# NixieDriver.net
KiCad netlist of a schematic drawn in EAGLE
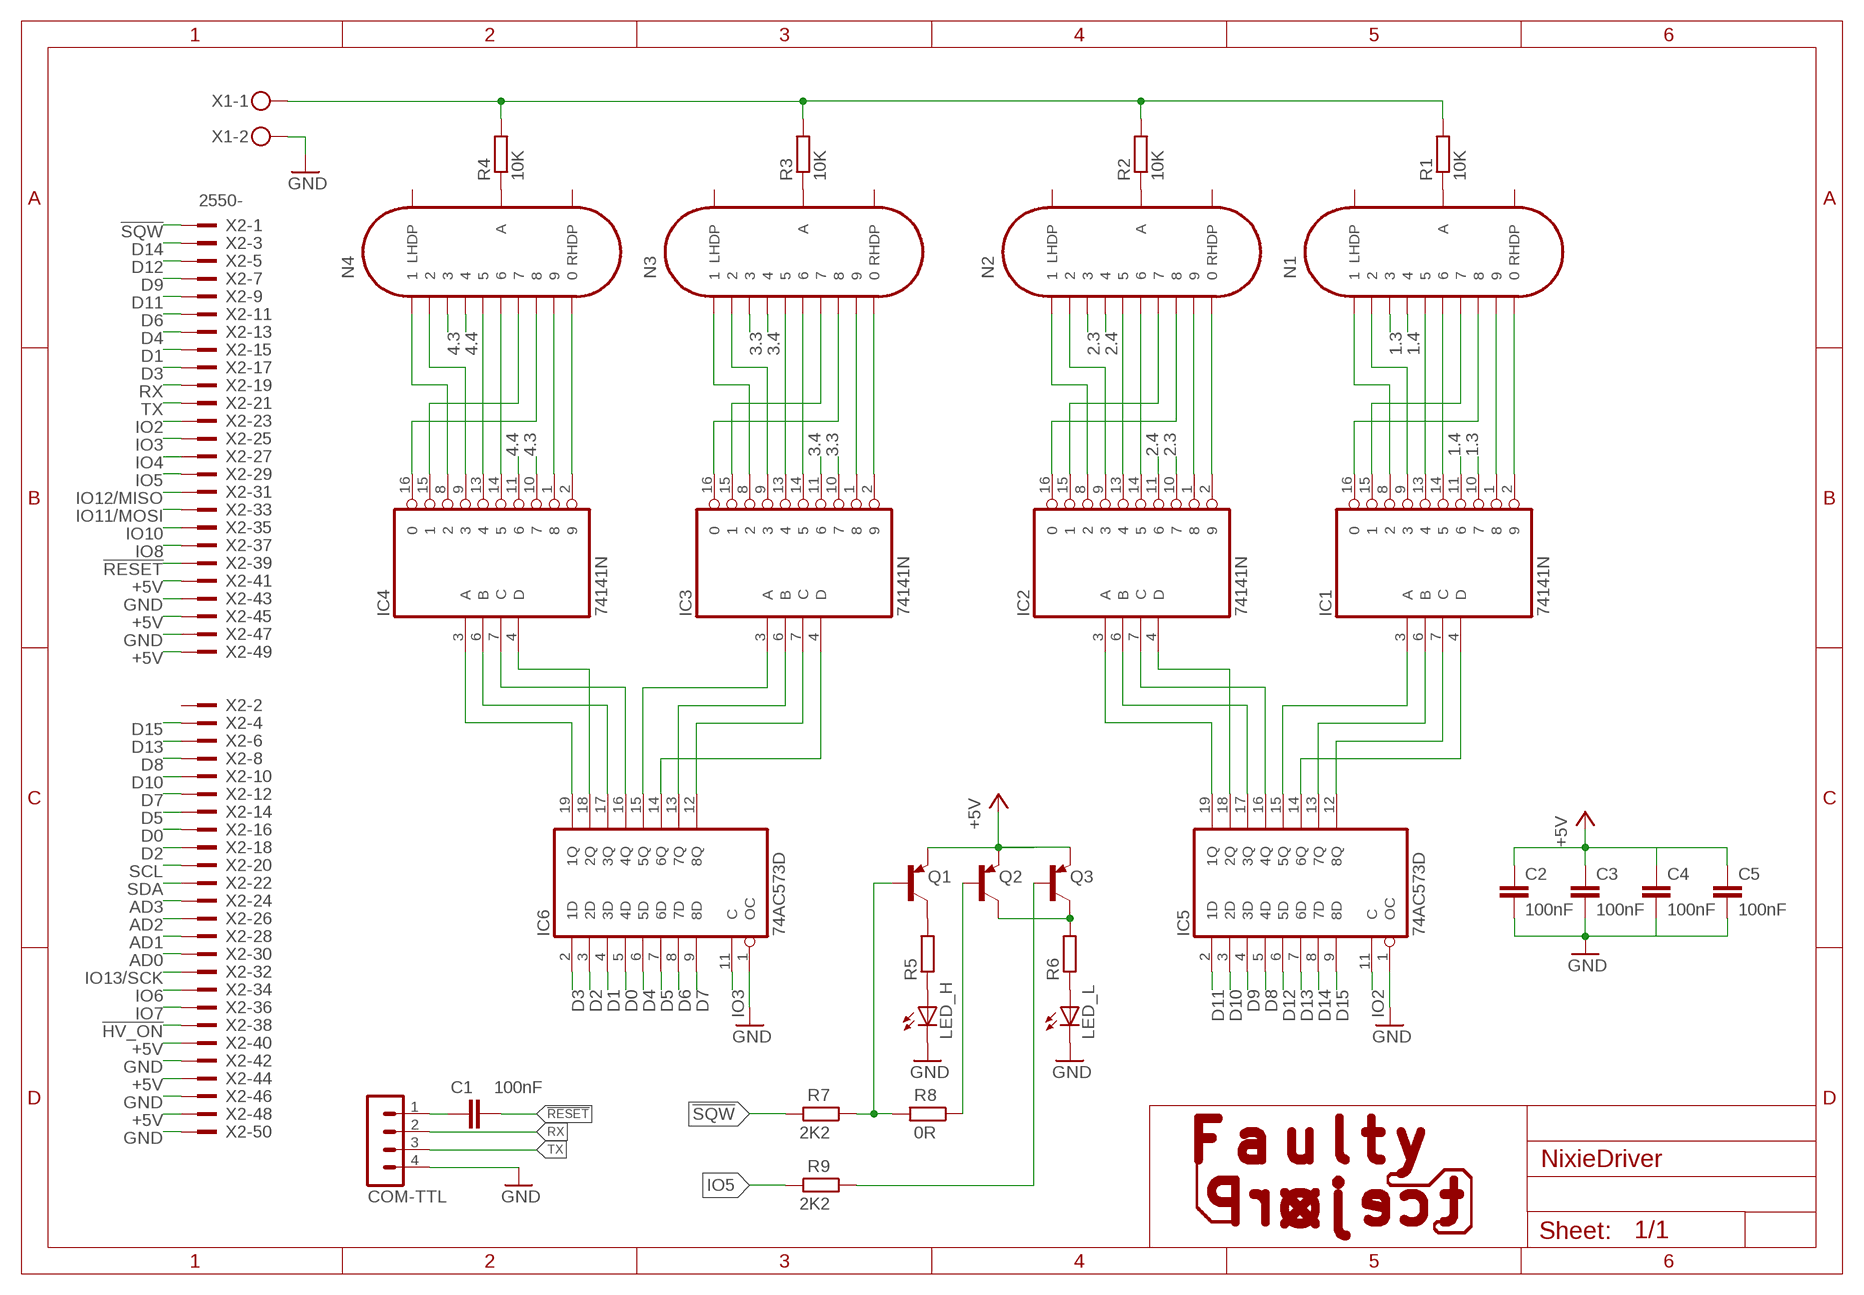
[diagram p0: schematic, sheet 1]

(export (version "E")
  (design (tool "Eeschema 10.0.6"))
  (components
    (comp (ref "C1")
      (value "100nF")
      (footprint "eagle-import:C1210")
      (libsource (lib "eagle-import") (part "C-EUC1210"))
    )
    (comp (ref "C2")
      (value "100nF")
      (footprint "eagle-import:C1210")
      (libsource (lib "eagle-import") (part "C-EUC1210"))
    )
    (comp (ref "C3")
      (value "100nF")
      (footprint "eagle-import:C1210")
      (libsource (lib "eagle-import") (part "C-EUC1210"))
    )
    (comp (ref "C4")
      (value "100nF")
      (footprint "eagle-import:C1210")
      (libsource (lib "eagle-import") (part "C-EUC1210"))
    )
    (comp (ref "C5")
      (value "100nF")
      (footprint "eagle-import:C1210")
      (libsource (lib "eagle-import") (part "C-EUC1210"))
    )
    (comp (ref "COM-TTL")
      (value "MA04-1")
      (footprint "eagle-import:MA04-1")
      (libsource (lib "eagle-import") (part "MA04-1"))
    )
    (comp (ref "IC1")
      (value "74141N")
      (footprint "eagle-import:DIL16")
      (libsource (lib "eagle-import") (part "74141N"))
    )
    (comp (ref "IC2")
      (value "74141N")
      (footprint "eagle-import:DIL16")
      (libsource (lib "eagle-import") (part "74141N"))
    )
    (comp (ref "IC3")
      (value "74141N")
      (footprint "eagle-import:DIL16")
      (libsource (lib "eagle-import") (part "74141N"))
    )
    (comp (ref "IC4")
      (value "74141N")
      (footprint "eagle-import:DIL16")
      (libsource (lib "eagle-import") (part "74141N"))
    )
    (comp (ref "IC5")
      (value "74AC573D")
      (footprint "eagle-import:SO20W")
      (libsource (lib "eagle-import") (part "74573DAC"))
    )
    (comp (ref "IC6")
      (value "74AC573D")
      (footprint "eagle-import:SO20W")
      (libsource (lib "eagle-import") (part "74573DAC"))
    )
    (comp (ref "LED_H")
      (value "LED5MM")
      (footprint "eagle-import:LED5MM")
      (libsource (lib "eagle-import") (part "LED5MM"))
    )
    (comp (ref "LED_L")
      (value "LED5MM")
      (footprint "eagle-import:LED5MM")
      (libsource (lib "eagle-import") (part "LED5MM"))
    )
    (comp (ref "N1")
      (value "IN-14")
      (footprint "eagle-import:IN-14")
      (libsource (lib "eagle-import") (part "IN-14"))
    )
    (comp (ref "N2")
      (value "IN-14")
      (footprint "eagle-import:IN-14")
      (libsource (lib "eagle-import") (part "IN-14"))
    )
    (comp (ref "N3")
      (value "IN-14")
      (footprint "eagle-import:IN-14")
      (libsource (lib "eagle-import") (part "IN-14"))
    )
    (comp (ref "N4")
      (value "IN-14")
      (footprint "eagle-import:IN-14")
      (libsource (lib "eagle-import") (part "IN-14"))
    )
    (comp (ref "Q1")
      (value "BF621-PNP-SOT98-BCE")
      (footprint "eagle-import:SOT89-BCE")
      (libsource (lib "eagle-import") (part "-PNP-SOT98-BCEBF621"))
    )
    (comp (ref "Q2")
      (value "BF621-PNP-SOT98-BCE")
      (footprint "eagle-import:SOT89-BCE")
      (libsource (lib "eagle-import") (part "-PNP-SOT98-BCEBF621"))
    )
    (comp (ref "Q3")
      (value "BF621-PNP-SOT98-BCE")
      (footprint "eagle-import:SOT89-BCE")
      (libsource (lib "eagle-import") (part "-PNP-SOT98-BCEBF621"))
    )
    (comp (ref "R1")
      (value "10K")
      (footprint "eagle-import:0309V")
      (libsource (lib "eagle-import") (part "R-EU_0309/V"))
    )
    (comp (ref "R2")
      (value "10K")
      (footprint "eagle-import:0309V")
      (libsource (lib "eagle-import") (part "R-EU_0309/V"))
    )
    (comp (ref "R3")
      (value "10K")
      (footprint "eagle-import:0309V")
      (libsource (lib "eagle-import") (part "R-EU_0309/V"))
    )
    (comp (ref "R4")
      (value "10K")
      (footprint "eagle-import:0309V")
      (libsource (lib "eagle-import") (part "R-EU_0309/V"))
    )
    (comp (ref "R5")
      (value "R-EU_M1206")
      (footprint "eagle-import:M1206")
      (libsource (lib "eagle-import") (part "R-EU_M1206"))
    )
    (comp (ref "R6")
      (value "R-EU_M1206")
      (footprint "eagle-import:M1206")
      (libsource (lib "eagle-import") (part "R-EU_M1206"))
    )
    (comp (ref "R7")
      (value "2K2")
      (footprint "eagle-import:M1406")
      (libsource (lib "eagle-import") (part "R-EU_M1406"))
    )
    (comp (ref "R8")
      (value "0R")
      (footprint "eagle-import:M1406")
      (libsource (lib "eagle-import") (part "R-EU_M1406"))
    )
    (comp (ref "R9")
      (value "2K2")
      (footprint "eagle-import:M1206")
      (libsource (lib "eagle-import") (part "R-EU_M1206"))
    )
    (comp (ref "X1")
      (value "MKDSN1,5/2-5,08")
      (footprint "eagle-import:MKDSN1,5_2-5,08")
      (libsource (lib "eagle-import") (part "MKDSN1,5/2-5,08"))
    )
    (comp (ref "X2")
      (value "2550-")
      (footprint "eagle-import:PAK100_2500-50")
      (libsource (lib "eagle-import") (part "2550-"))
    )
  )
  (nets
    (net (code "1") (name "+5V") (class "Default")
      (node (ref "C2") (pin "1") (pinfunction "1_1") (pintype "passive"))
      (node (ref "C3") (pin "1") (pinfunction "1_1") (pintype "passive"))
      (node (ref "C4") (pin "1") (pinfunction "1_1") (pintype "passive"))
      (node (ref "C5") (pin "1") (pinfunction "1_1") (pintype "passive"))
      (node (ref "Q1") (pin "E") (pinfunction "E_E") (pintype "passive"))
      (node (ref "Q2") (pin "E") (pinfunction "E_E") (pintype "passive"))
      (node (ref "Q3") (pin "E") (pinfunction "E_E") (pintype "passive"))
      (node (ref "X2") (pin "40") (pinfunction "KL_40") (pintype "passive"))
      (node (ref "X2") (pin "41") (pinfunction "KL_41") (pintype "passive"))
      (node (ref "X2") (pin "44") (pinfunction "KL_44") (pintype "passive"))
      (node (ref "X2") (pin "45") (pinfunction "KL_45") (pintype "passive"))
      (node (ref "X2") (pin "48") (pinfunction "KL_48") (pintype "passive"))
      (node (ref "X2") (pin "49") (pinfunction "KL_49") (pintype "passive"))
    )
    (net (code "2") (name "/1.3") (class "Default")
      (node (ref "IC1") (pin "10") (pinfunction "7_10") (pintype "open_collector"))
      (node (ref "N1") (pin "3") (pinfunction "3_3") (pintype "bidirectional"))
    )
    (net (code "3") (name "/1.4") (class "Default")
      (node (ref "IC1") (pin "11") (pinfunction "6_11") (pintype "open_collector"))
      (node (ref "N1") (pin "4") (pinfunction "4_4") (pintype "bidirectional"))
    )
    (net (code "4") (name "/2.3") (class "Default")
      (node (ref "IC2") (pin "10") (pinfunction "7_10") (pintype "open_collector"))
      (node (ref "N2") (pin "3") (pinfunction "3_3") (pintype "bidirectional"))
    )
    (net (code "5") (name "/2.4") (class "Default")
      (node (ref "IC2") (pin "11") (pinfunction "6_11") (pintype "open_collector"))
      (node (ref "N2") (pin "4") (pinfunction "4_4") (pintype "bidirectional"))
    )
    (net (code "6") (name "/3.3") (class "Default")
      (node (ref "IC3") (pin "10") (pinfunction "7_10") (pintype "open_collector"))
      (node (ref "N3") (pin "3") (pinfunction "3_3") (pintype "bidirectional"))
    )
    (net (code "7") (name "/3.4") (class "Default")
      (node (ref "IC3") (pin "11") (pinfunction "6_11") (pintype "open_collector"))
      (node (ref "N3") (pin "4") (pinfunction "4_4") (pintype "bidirectional"))
    )
    (net (code "8") (name "/4.3") (class "Default")
      (node (ref "IC4") (pin "10") (pinfunction "7_10") (pintype "open_collector"))
      (node (ref "N4") (pin "3") (pinfunction "3_3") (pintype "bidirectional"))
    )
    (net (code "9") (name "/4.4") (class "Default")
      (node (ref "IC4") (pin "11") (pinfunction "6_11") (pintype "open_collector"))
      (node (ref "N4") (pin "4") (pinfunction "4_4") (pintype "bidirectional"))
    )
    (net (code "10") (name "/AD0") (class "Default")
      (node (ref "X2") (pin "30") (pinfunction "KL_30") (pintype "passive"))
    )
    (net (code "11") (name "/AD1") (class "Default")
      (node (ref "X2") (pin "28") (pinfunction "KL_28") (pintype "passive"))
    )
    (net (code "12") (name "/AD2") (class "Default")
      (node (ref "X2") (pin "26") (pinfunction "KL_26") (pintype "passive"))
    )
    (net (code "13") (name "/AD3") (class "Default")
      (node (ref "X2") (pin "24") (pinfunction "KL_24") (pintype "passive"))
    )
    (net (code "14") (name "/D0") (class "Default")
      (node (ref "IC6") (pin "5") (pinfunction "4D_5") (pintype "input"))
      (node (ref "X2") (pin "16") (pinfunction "KL_16") (pintype "passive"))
    )
    (net (code "15") (name "/D1") (class "Default")
      (node (ref "IC6") (pin "4") (pinfunction "3D_4") (pintype "input"))
      (node (ref "X2") (pin "15") (pinfunction "KL_15") (pintype "passive"))
    )
    (net (code "16") (name "/D2") (class "Default")
      (node (ref "IC6") (pin "3") (pinfunction "2D_3") (pintype "input"))
      (node (ref "X2") (pin "18") (pinfunction "KL_18") (pintype "passive"))
    )
    (net (code "17") (name "/D3") (class "Default")
      (node (ref "IC6") (pin "2") (pinfunction "1D_2") (pintype "input"))
      (node (ref "X2") (pin "17") (pinfunction "KL_17") (pintype "passive"))
    )
    (net (code "18") (name "/D4") (class "Default")
      (node (ref "IC6") (pin "6") (pinfunction "5D_6") (pintype "input"))
      (node (ref "X2") (pin "13") (pinfunction "KL_13") (pintype "passive"))
    )
    (net (code "19") (name "/D5") (class "Default")
      (node (ref "IC6") (pin "7") (pinfunction "6D_7") (pintype "input"))
      (node (ref "X2") (pin "14") (pinfunction "KL_14") (pintype "passive"))
    )
    (net (code "20") (name "/D6") (class "Default")
      (node (ref "IC6") (pin "8") (pinfunction "7D_8") (pintype "input"))
      (node (ref "X2") (pin "11") (pinfunction "KL_11") (pintype "passive"))
    )
    (net (code "21") (name "/D7") (class "Default")
      (node (ref "IC6") (pin "9") (pinfunction "8D_9") (pintype "input"))
      (node (ref "X2") (pin "12") (pinfunction "KL_12") (pintype "passive"))
    )
    (net (code "22") (name "/D8") (class "Default")
      (node (ref "IC5") (pin "5") (pinfunction "4D_5") (pintype "input"))
      (node (ref "X2") (pin "8") (pinfunction "KL_8") (pintype "passive"))
    )
    (net (code "23") (name "/D9") (class "Default")
      (node (ref "IC5") (pin "4") (pinfunction "3D_4") (pintype "input"))
      (node (ref "X2") (pin "7") (pinfunction "KL_7") (pintype "passive"))
    )
    (net (code "24") (name "/D10") (class "Default")
      (node (ref "IC5") (pin "3") (pinfunction "2D_3") (pintype "input"))
      (node (ref "X2") (pin "10") (pinfunction "KL_10") (pintype "passive"))
    )
    (net (code "25") (name "/D11") (class "Default")
      (node (ref "IC5") (pin "2") (pinfunction "1D_2") (pintype "input"))
      (node (ref "X2") (pin "9") (pinfunction "KL_9") (pintype "passive"))
    )
    (net (code "26") (name "/D12") (class "Default")
      (node (ref "IC5") (pin "6") (pinfunction "5D_6") (pintype "input"))
      (node (ref "X2") (pin "5") (pinfunction "KL_5") (pintype "passive"))
    )
    (net (code "27") (name "/D13") (class "Default")
      (node (ref "IC5") (pin "7") (pinfunction "6D_7") (pintype "input"))
      (node (ref "X2") (pin "6") (pinfunction "KL_6") (pintype "passive"))
    )
    (net (code "28") (name "/D14") (class "Default")
      (node (ref "IC5") (pin "8") (pinfunction "7D_8") (pintype "input"))
      (node (ref "X2") (pin "3") (pinfunction "KL_3") (pintype "passive"))
    )
    (net (code "29") (name "/D15") (class "Default")
      (node (ref "IC5") (pin "9") (pinfunction "8D_9") (pintype "input"))
      (node (ref "X2") (pin "4") (pinfunction "KL_4") (pintype "passive"))
    )
    (net (code "30") (name "/IO2") (class "Default")
      (node (ref "IC5") (pin "11") (pinfunction "C_11") (pintype "input"))
      (node (ref "X2") (pin "23") (pinfunction "KL_23") (pintype "passive"))
    )
    (net (code "31") (name "/IO3") (class "Default")
      (node (ref "IC6") (pin "11") (pinfunction "C_11") (pintype "input"))
      (node (ref "X2") (pin "25") (pinfunction "KL_25") (pintype "passive"))
    )
    (net (code "32") (name "/IO4") (class "Default")
      (node (ref "X2") (pin "27") (pinfunction "KL_27") (pintype "passive"))
    )
    (net (code "33") (name "/IO6") (class "Default")
      (node (ref "X2") (pin "34") (pinfunction "KL_34") (pintype "passive"))
    )
    (net (code "34") (name "/IO7") (class "Default")
      (node (ref "X2") (pin "36") (pinfunction "KL_36") (pintype "passive"))
    )
    (net (code "35") (name "/IO8") (class "Default")
      (node (ref "X2") (pin "37") (pinfunction "KL_37") (pintype "passive"))
    )
    (net (code "36") (name "/IO10") (class "Default")
      (node (ref "X2") (pin "35") (pinfunction "KL_35") (pintype "passive"))
    )
    (net (code "37") (name "/IO11{slash}MOSI") (class "Default")
      (node (ref "X2") (pin "33") (pinfunction "KL_33") (pintype "passive"))
    )
    (net (code "38") (name "/IO12{slash}MISO") (class "Default")
      (node (ref "X2") (pin "31") (pinfunction "KL_31") (pintype "passive"))
    )
    (net (code "39") (name "/IO13{slash}SCK") (class "Default")
      (node (ref "X2") (pin "32") (pinfunction "KL_32") (pintype "passive"))
    )
    (net (code "40") (name "/SCL") (class "Default")
      (node (ref "X2") (pin "20") (pinfunction "KL_20") (pintype "passive"))
    )
    (net (code "41") (name "/SDA") (class "Default")
      (node (ref "X2") (pin "22") (pinfunction "KL_22") (pintype "passive"))
    )
    (net (code "42") (name "/~{HV_ON}") (class "Default")
      (node (ref "X2") (pin "38") (pinfunction "KL_38") (pintype "passive"))
    )
    (net (code "43") (name "/~{RESET}") (class "Default")
      (node (ref "C1") (pin "2") (pinfunction "2_2") (pintype "passive"))
      (node (ref "X2") (pin "39") (pinfunction "KL_39") (pintype "passive"))
    )
    (net (code "44") (name "/~{SQW}") (class "Default")
      (node (ref "R7") (pin "2") (pinfunction "2_2") (pintype "passive"))
      (node (ref "X2") (pin "1") (pinfunction "KL_1") (pintype "passive"))
    )
    (net (code "45") (name "GND") (class "Default")
      (node (ref "C2") (pin "2") (pinfunction "2_2") (pintype "passive"))
      (node (ref "C3") (pin "2") (pinfunction "2_2") (pintype "passive"))
      (node (ref "C4") (pin "2") (pinfunction "2_2") (pintype "passive"))
      (node (ref "C5") (pin "2") (pinfunction "2_2") (pintype "passive"))
      (node (ref "COM-TTL") (pin "4") (pinfunction "4_4") (pintype "passive"))
      (node (ref "IC5") (pin "1") (pinfunction "OC_1") (pintype "input"))
      (node (ref "IC6") (pin "1") (pinfunction "OC_1") (pintype "input"))
      (node (ref "LED_H") (pin "K") (pinfunction "C_K") (pintype "passive"))
      (node (ref "LED_L") (pin "K") (pinfunction "C_K") (pintype "passive"))
      (node (ref "X1") (pin "2") (pinfunction "KL_2") (pintype "passive"))
      (node (ref "X2") (pin "42") (pinfunction "KL_42") (pintype "passive"))
      (node (ref "X2") (pin "43") (pinfunction "KL_43") (pintype "passive"))
      (node (ref "X2") (pin "46") (pinfunction "KL_46") (pintype "passive"))
      (node (ref "X2") (pin "47") (pinfunction "KL_47") (pintype "passive"))
      (node (ref "X2") (pin "50") (pinfunction "KL_50") (pintype "passive"))
    )
    (net (code "46") (name "IO5") (class "Default")
      (node (ref "R9") (pin "2") (pinfunction "2_2") (pintype "passive"))
      (node (ref "X2") (pin "29") (pinfunction "KL_29") (pintype "passive"))
    )
    (net (code "47") (name "Net-(C1-Pad1)") (class "Default")
      (node (ref "C1") (pin "1") (pinfunction "1_1") (pintype "passive"))
      (node (ref "COM-TTL") (pin "1") (pinfunction "1_1") (pintype "passive"))
    )
    (net (code "48") (name "Net-(IC1A-0)") (class "Default")
      (node (ref "IC1") (pin "16") (pinfunction "0_16") (pintype "open_collector"))
      (node (ref "N1") (pin "8") (pinfunction "8_8") (pintype "bidirectional"))
    )
    (net (code "49") (name "Net-(IC1A-1)") (class "Default")
      (node (ref "IC1") (pin "15") (pinfunction "1_15") (pintype "open_collector"))
      (node (ref "N1") (pin "7") (pinfunction "7_7") (pintype "bidirectional"))
    )
    (net (code "50") (name "Net-(IC1A-2)") (class "Default")
      (node (ref "IC1") (pin "8") (pinfunction "2_8") (pintype "open_collector"))
      (node (ref "N1") (pin "1") (pinfunction "1_1") (pintype "bidirectional"))
    )
    (net (code "51") (name "Net-(IC1A-3)") (class "Default")
      (node (ref "IC1") (pin "9") (pinfunction "3_9") (pintype "open_collector"))
      (node (ref "N1") (pin "2") (pinfunction "2_2") (pintype "bidirectional"))
    )
    (net (code "52") (name "Net-(IC1A-4)") (class "Default")
      (node (ref "IC1") (pin "13") (pinfunction "4_13") (pintype "open_collector"))
      (node (ref "N1") (pin "5") (pinfunction "5_5") (pintype "bidirectional"))
    )
    (net (code "53") (name "Net-(IC1A-5)") (class "Default")
      (node (ref "IC1") (pin "14") (pinfunction "5_14") (pintype "open_collector"))
      (node (ref "N1") (pin "6") (pinfunction "6_6") (pintype "bidirectional"))
    )
    (net (code "54") (name "Net-(IC1A-8)") (class "Default")
      (node (ref "IC1") (pin "1") (pinfunction "8_1") (pintype "open_collector"))
      (node (ref "N1") (pin "9") (pinfunction "9_9") (pintype "bidirectional"))
    )
    (net (code "55") (name "Net-(IC1A-9)") (class "Default")
      (node (ref "IC1") (pin "2") (pinfunction "9_2") (pintype "open_collector"))
      (node (ref "N1") (pin "0") (pinfunction "0_0") (pintype "bidirectional"))
    )
    (net (code "56") (name "Net-(IC1A-A)") (class "Default")
      (node (ref "IC1") (pin "3") (pinfunction "A_3") (pintype "input"))
      (node (ref "IC5") (pin "15") (pinfunction "5Q_15") (pintype "tri_state"))
    )
    (net (code "57") (name "Net-(IC1A-B)") (class "Default")
      (node (ref "IC1") (pin "6") (pinfunction "B_6") (pintype "input"))
      (node (ref "IC5") (pin "13") (pinfunction "7Q_13") (pintype "tri_state"))
    )
    (net (code "58") (name "Net-(IC1A-C)") (class "Default")
      (node (ref "IC1") (pin "7") (pinfunction "C_7") (pintype "input"))
      (node (ref "IC5") (pin "12") (pinfunction "8Q_12") (pintype "tri_state"))
    )
    (net (code "59") (name "Net-(IC1A-D)") (class "Default")
      (node (ref "IC1") (pin "4") (pinfunction "D_4") (pintype "input"))
      (node (ref "IC5") (pin "14") (pinfunction "6Q_14") (pintype "tri_state"))
    )
    (net (code "60") (name "Net-(IC2A-0)") (class "Default")
      (node (ref "IC2") (pin "16") (pinfunction "0_16") (pintype "open_collector"))
      (node (ref "N2") (pin "8") (pinfunction "8_8") (pintype "bidirectional"))
    )
    (net (code "61") (name "Net-(IC2A-1)") (class "Default")
      (node (ref "IC2") (pin "15") (pinfunction "1_15") (pintype "open_collector"))
      (node (ref "N2") (pin "7") (pinfunction "7_7") (pintype "bidirectional"))
    )
    (net (code "62") (name "Net-(IC2A-2)") (class "Default")
      (node (ref "IC2") (pin "8") (pinfunction "2_8") (pintype "open_collector"))
      (node (ref "N2") (pin "1") (pinfunction "1_1") (pintype "bidirectional"))
    )
    (net (code "63") (name "Net-(IC2A-3)") (class "Default")
      (node (ref "IC2") (pin "9") (pinfunction "3_9") (pintype "open_collector"))
      (node (ref "N2") (pin "2") (pinfunction "2_2") (pintype "bidirectional"))
    )
    (net (code "64") (name "Net-(IC2A-4)") (class "Default")
      (node (ref "IC2") (pin "13") (pinfunction "4_13") (pintype "open_collector"))
      (node (ref "N2") (pin "5") (pinfunction "5_5") (pintype "bidirectional"))
    )
    (net (code "65") (name "Net-(IC2A-5)") (class "Default")
      (node (ref "IC2") (pin "14") (pinfunction "5_14") (pintype "open_collector"))
      (node (ref "N2") (pin "6") (pinfunction "6_6") (pintype "bidirectional"))
    )
    (net (code "66") (name "Net-(IC2A-8)") (class "Default")
      (node (ref "IC2") (pin "1") (pinfunction "8_1") (pintype "open_collector"))
      (node (ref "N2") (pin "9") (pinfunction "9_9") (pintype "bidirectional"))
    )
    (net (code "67") (name "Net-(IC2A-9)") (class "Default")
      (node (ref "IC2") (pin "2") (pinfunction "9_2") (pintype "open_collector"))
      (node (ref "N2") (pin "0") (pinfunction "0_0") (pintype "bidirectional"))
    )
    (net (code "68") (name "Net-(IC2A-A)") (class "Default")
      (node (ref "IC2") (pin "3") (pinfunction "A_3") (pintype "input"))
      (node (ref "IC5") (pin "19") (pinfunction "1Q_19") (pintype "tri_state"))
    )
    (net (code "69") (name "Net-(IC2A-B)") (class "Default")
      (node (ref "IC2") (pin "6") (pinfunction "B_6") (pintype "input"))
      (node (ref "IC5") (pin "17") (pinfunction "3Q_17") (pintype "tri_state"))
    )
    (net (code "70") (name "Net-(IC2A-C)") (class "Default")
      (node (ref "IC2") (pin "7") (pinfunction "C_7") (pintype "input"))
      (node (ref "IC5") (pin "16") (pinfunction "4Q_16") (pintype "tri_state"))
    )
    (net (code "71") (name "Net-(IC2A-D)") (class "Default")
      (node (ref "IC2") (pin "4") (pinfunction "D_4") (pintype "input"))
      (node (ref "IC5") (pin "18") (pinfunction "2Q_18") (pintype "tri_state"))
    )
    (net (code "72") (name "Net-(IC3A-0)") (class "Default")
      (node (ref "IC3") (pin "16") (pinfunction "0_16") (pintype "open_collector"))
      (node (ref "N3") (pin "8") (pinfunction "8_8") (pintype "bidirectional"))
    )
    (net (code "73") (name "Net-(IC3A-1)") (class "Default")
      (node (ref "IC3") (pin "15") (pinfunction "1_15") (pintype "open_collector"))
      (node (ref "N3") (pin "7") (pinfunction "7_7") (pintype "bidirectional"))
    )
    (net (code "74") (name "Net-(IC3A-2)") (class "Default")
      (node (ref "IC3") (pin "8") (pinfunction "2_8") (pintype "open_collector"))
      (node (ref "N3") (pin "1") (pinfunction "1_1") (pintype "bidirectional"))
    )
    (net (code "75") (name "Net-(IC3A-3)") (class "Default")
      (node (ref "IC3") (pin "9") (pinfunction "3_9") (pintype "open_collector"))
      (node (ref "N3") (pin "2") (pinfunction "2_2") (pintype "bidirectional"))
    )
    (net (code "76") (name "Net-(IC3A-4)") (class "Default")
      (node (ref "IC3") (pin "13") (pinfunction "4_13") (pintype "open_collector"))
      (node (ref "N3") (pin "5") (pinfunction "5_5") (pintype "bidirectional"))
    )
    (net (code "77") (name "Net-(IC3A-5)") (class "Default")
      (node (ref "IC3") (pin "14") (pinfunction "5_14") (pintype "open_collector"))
      (node (ref "N3") (pin "6") (pinfunction "6_6") (pintype "bidirectional"))
    )
    (net (code "78") (name "Net-(IC3A-8)") (class "Default")
      (node (ref "IC3") (pin "1") (pinfunction "8_1") (pintype "open_collector"))
      (node (ref "N3") (pin "9") (pinfunction "9_9") (pintype "bidirectional"))
    )
    (net (code "79") (name "Net-(IC3A-9)") (class "Default")
      (node (ref "IC3") (pin "2") (pinfunction "9_2") (pintype "open_collector"))
      (node (ref "N3") (pin "0") (pinfunction "0_0") (pintype "bidirectional"))
    )
    (net (code "80") (name "Net-(IC3A-A)") (class "Default")
      (node (ref "IC3") (pin "3") (pinfunction "A_3") (pintype "input"))
      (node (ref "IC6") (pin "15") (pinfunction "5Q_15") (pintype "tri_state"))
    )
    (net (code "81") (name "Net-(IC3A-B)") (class "Default")
      (node (ref "IC3") (pin "6") (pinfunction "B_6") (pintype "input"))
      (node (ref "IC6") (pin "13") (pinfunction "7Q_13") (pintype "tri_state"))
    )
    (net (code "82") (name "Net-(IC3A-C)") (class "Default")
      (node (ref "IC3") (pin "7") (pinfunction "C_7") (pintype "input"))
      (node (ref "IC6") (pin "12") (pinfunction "8Q_12") (pintype "tri_state"))
    )
    (net (code "83") (name "Net-(IC3A-D)") (class "Default")
      (node (ref "IC3") (pin "4") (pinfunction "D_4") (pintype "input"))
      (node (ref "IC6") (pin "14") (pinfunction "6Q_14") (pintype "tri_state"))
    )
    (net (code "84") (name "Net-(IC4A-0)") (class "Default")
      (node (ref "IC4") (pin "16") (pinfunction "0_16") (pintype "open_collector"))
      (node (ref "N4") (pin "8") (pinfunction "8_8") (pintype "bidirectional"))
    )
    (net (code "85") (name "Net-(IC4A-1)") (class "Default")
      (node (ref "IC4") (pin "15") (pinfunction "1_15") (pintype "open_collector"))
      (node (ref "N4") (pin "7") (pinfunction "7_7") (pintype "bidirectional"))
    )
    (net (code "86") (name "Net-(IC4A-2)") (class "Default")
      (node (ref "IC4") (pin "8") (pinfunction "2_8") (pintype "open_collector"))
      (node (ref "N4") (pin "1") (pinfunction "1_1") (pintype "bidirectional"))
    )
    (net (code "87") (name "Net-(IC4A-3)") (class "Default")
      (node (ref "IC4") (pin "9") (pinfunction "3_9") (pintype "open_collector"))
      (node (ref "N4") (pin "2") (pinfunction "2_2") (pintype "bidirectional"))
    )
    (net (code "88") (name "Net-(IC4A-4)") (class "Default")
      (node (ref "IC4") (pin "13") (pinfunction "4_13") (pintype "open_collector"))
      (node (ref "N4") (pin "5") (pinfunction "5_5") (pintype "bidirectional"))
    )
    (net (code "89") (name "Net-(IC4A-5)") (class "Default")
      (node (ref "IC4") (pin "14") (pinfunction "5_14") (pintype "open_collector"))
      (node (ref "N4") (pin "6") (pinfunction "6_6") (pintype "bidirectional"))
    )
    (net (code "90") (name "Net-(IC4A-8)") (class "Default")
      (node (ref "IC4") (pin "1") (pinfunction "8_1") (pintype "open_collector"))
      (node (ref "N4") (pin "9") (pinfunction "9_9") (pintype "bidirectional"))
    )
    (net (code "91") (name "Net-(IC4A-9)") (class "Default")
      (node (ref "IC4") (pin "2") (pinfunction "9_2") (pintype "open_collector"))
      (node (ref "N4") (pin "0") (pinfunction "0_0") (pintype "bidirectional"))
    )
    (net (code "92") (name "Net-(IC4A-A)") (class "Default")
      (node (ref "IC4") (pin "3") (pinfunction "A_3") (pintype "input"))
      (node (ref "IC6") (pin "19") (pinfunction "1Q_19") (pintype "tri_state"))
    )
    (net (code "93") (name "Net-(IC4A-B)") (class "Default")
      (node (ref "IC4") (pin "6") (pinfunction "B_6") (pintype "input"))
      (node (ref "IC6") (pin "17") (pinfunction "3Q_17") (pintype "tri_state"))
    )
    (net (code "94") (name "Net-(IC4A-C)") (class "Default")
      (node (ref "IC4") (pin "7") (pinfunction "C_7") (pintype "input"))
      (node (ref "IC6") (pin "16") (pinfunction "4Q_16") (pintype "tri_state"))
    )
    (net (code "95") (name "Net-(IC4A-D)") (class "Default")
      (node (ref "IC4") (pin "4") (pinfunction "D_4") (pintype "input"))
      (node (ref "IC6") (pin "18") (pinfunction "2Q_18") (pintype "tri_state"))
    )
    (net (code "96") (name "Net-(LED_H-PadA)") (class "Default")
      (node (ref "LED_H") (pin "A") (pinfunction "A_A") (pintype "passive"))
      (node (ref "R5") (pin "1") (pinfunction "1_1") (pintype "passive"))
    )
    (net (code "97") (name "Net-(LED_L-PadA)") (class "Default")
      (node (ref "LED_L") (pin "A") (pinfunction "A_A") (pintype "passive"))
      (node (ref "R6") (pin "1") (pinfunction "1_1") (pintype "passive"))
    )
    (net (code "98") (name "Net-(N1-PadA)") (class "Default")
      (node (ref "N1") (pin "A") (pinfunction "A_A") (pintype "bidirectional"))
      (node (ref "R1") (pin "1") (pinfunction "1_1") (pintype "passive"))
    )
    (net (code "99") (name "Net-(N2-PadA)") (class "Default")
      (node (ref "N2") (pin "A") (pinfunction "A_A") (pintype "bidirectional"))
      (node (ref "R2") (pin "1") (pinfunction "1_1") (pintype "passive"))
    )
    (net (code "100") (name "Net-(N3-PadA)") (class "Default")
      (node (ref "N3") (pin "A") (pinfunction "A_A") (pintype "bidirectional"))
      (node (ref "R3") (pin "1") (pinfunction "1_1") (pintype "passive"))
    )
    (net (code "101") (name "Net-(N4-PadA)") (class "Default")
      (node (ref "N4") (pin "A") (pinfunction "A_A") (pintype "bidirectional"))
      (node (ref "R4") (pin "1") (pinfunction "1_1") (pintype "passive"))
    )
    (net (code "102") (name "Net-(Q1-PadB)") (class "Default")
      (node (ref "Q1") (pin "B") (pinfunction "B_B") (pintype "passive"))
      (node (ref "R7") (pin "1") (pinfunction "1_1") (pintype "passive"))
      (node (ref "R8") (pin "2") (pinfunction "2_2") (pintype "passive"))
    )
    (net (code "103") (name "Net-(Q1-PadC)") (class "Default")
      (node (ref "Q1") (pin "C") (pinfunction "C_C") (pintype "passive"))
      (node (ref "R5") (pin "2") (pinfunction "2_2") (pintype "passive"))
    )
    (net (code "104") (name "Net-(Q2-PadB)") (class "Default")
      (node (ref "Q2") (pin "B") (pinfunction "B_B") (pintype "passive"))
      (node (ref "R8") (pin "1") (pinfunction "1_1") (pintype "passive"))
    )
    (net (code "105") (name "Net-(Q2-PadC)") (class "Default")
      (node (ref "Q2") (pin "C") (pinfunction "C_C") (pintype "passive"))
      (node (ref "Q3") (pin "C") (pinfunction "C_C") (pintype "passive"))
      (node (ref "R6") (pin "2") (pinfunction "2_2") (pintype "passive"))
    )
    (net (code "106") (name "Net-(Q3-PadB)") (class "Default")
      (node (ref "Q3") (pin "B") (pinfunction "B_B") (pintype "passive"))
      (node (ref "R9") (pin "1") (pinfunction "1_1") (pintype "passive"))
    )
    (net (code "107") (name "Net-(X1A-KL)") (class "Default")
      (node (ref "R1") (pin "2") (pinfunction "2_2") (pintype "passive"))
      (node (ref "R2") (pin "2") (pinfunction "2_2") (pintype "passive"))
      (node (ref "R3") (pin "2") (pinfunction "2_2") (pintype "passive"))
      (node (ref "R4") (pin "2") (pinfunction "2_2") (pintype "passive"))
      (node (ref "X1") (pin "1") (pinfunction "KL_1") (pintype "passive"))
    )
    (net (code "108") (name "RX") (class "Default")
      (node (ref "COM-TTL") (pin "2") (pinfunction "2_2") (pintype "passive"))
      (node (ref "X2") (pin "19") (pinfunction "KL_19") (pintype "passive"))
    )
    (net (code "109") (name "TX") (class "Default")
      (node (ref "COM-TTL") (pin "3") (pinfunction "3_3") (pintype "passive"))
      (node (ref "X2") (pin "21") (pinfunction "KL_21") (pintype "passive"))
    )
    (net (code "110") (name "unconnected-(N1-PadLHDP)") (class "Default")
      (node (ref "N1") (pin "LHDP") (pinfunction "LHDP_LHDP") (pintype "bidirectional"))
    )
    (net (code "111") (name "unconnected-(N1-PadRHDP)") (class "Default")
      (node (ref "N1") (pin "RHDP") (pinfunction "RHDP_RHDP") (pintype "bidirectional"))
    )
    (net (code "112") (name "unconnected-(N2-PadLHDP)") (class "Default")
      (node (ref "N2") (pin "LHDP") (pinfunction "LHDP_LHDP") (pintype "bidirectional"))
    )
    (net (code "113") (name "unconnected-(N2-PadRHDP)") (class "Default")
      (node (ref "N2") (pin "RHDP") (pinfunction "RHDP_RHDP") (pintype "bidirectional"))
    )
    (net (code "114") (name "unconnected-(N3-PadLHDP)") (class "Default")
      (node (ref "N3") (pin "LHDP") (pinfunction "LHDP_LHDP") (pintype "bidirectional"))
    )
    (net (code "115") (name "unconnected-(N3-PadRHDP)") (class "Default")
      (node (ref "N3") (pin "RHDP") (pinfunction "RHDP_RHDP") (pintype "bidirectional"))
    )
    (net (code "116") (name "unconnected-(N4-PadLHDP)") (class "Default")
      (node (ref "N4") (pin "LHDP") (pinfunction "LHDP_LHDP") (pintype "bidirectional"))
    )
    (net (code "117") (name "unconnected-(N4-PadRHDP)") (class "Default")
      (node (ref "N4") (pin "RHDP") (pinfunction "RHDP_RHDP") (pintype "bidirectional"))
    )
    (net (code "118") (name "unconnected-(X2L-KL-Pad2)") (class "Default")
      (node (ref "X2") (pin "2") (pinfunction "KL_2") (pintype "passive"))
    )
  )
)
